# Receiver.net
KiCad netlist of a schematic drawn in Altium Designer
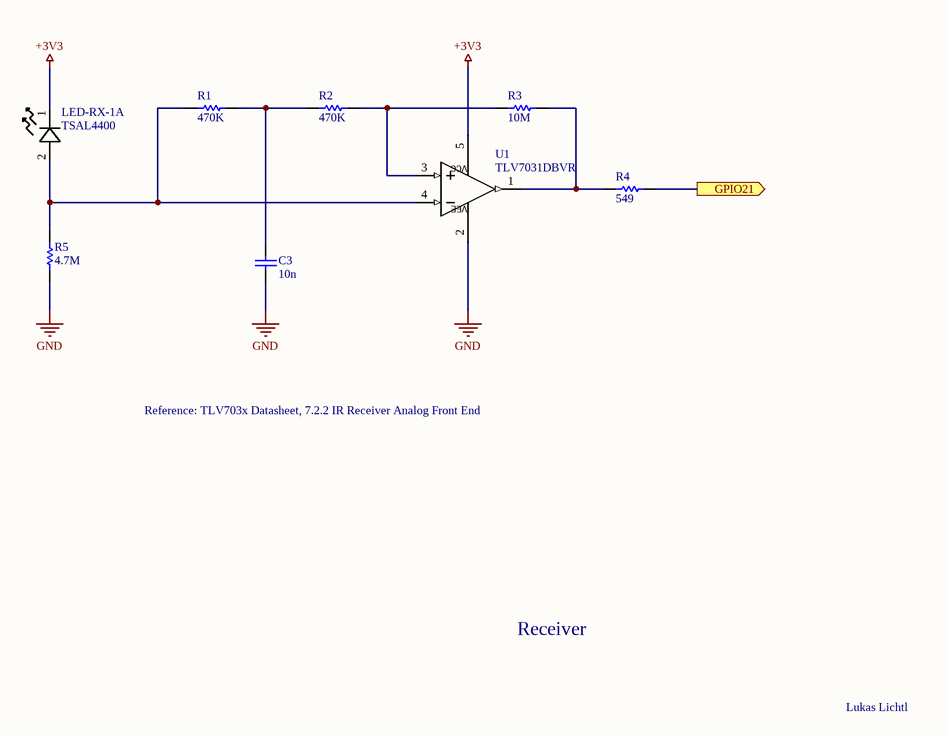
[diagram p0: Receiver.SchDoc]

(export (version "E")
  (design (tool "Eeschema 10.0.6"))
  (components
    (comp (ref "C3")
      (value "10n")
      (footprint "CAPC1608X90X35LL15T15")
      (fields
        (field (name "MANUFACTURER") "AVX Interconnect / Elco")
        (field (name "PART NUMBER") "0603ZC101KAT2A")
      )
      (libsource (lib "Altium Content Vault") (part "CAP"))
    )
    (comp (ref "LED-RX-1")
      (value "TSAL4400")
      (footprint "LED_RADIAL_TSAL4400")
      (description "Description")
      (fields (field (name "COPYRIGHT") "Copyright (C) 2025 Ultra Librarian. All rights reserved."))
      (libsource (lib "TSAL4400") (part "TSAL4400"))
    )
    (comp (ref "R1")
      (value "470K")
      (footprint "RESC1608X55X25NL10T15")
      (fields (field (name "MANUFACTURER") "Yageo") (field (name "PART NUMBER") "RC0603FR-07549RL"))
      (libsource (lib "Altium Content Vault") (part "RES"))
    )
    (comp (ref "R2")
      (value "470K")
      (footprint "RESC1608X55X25NL10T15")
      (fields (field (name "MANUFACTURER") "Yageo") (field (name "PART NUMBER") "RC0603FR-07549RL"))
      (libsource (lib "Altium Content Vault") (part "RES"))
    )
    (comp (ref "R3")
      (value "10M")
      (footprint "RESC1608X55X25NL10T15")
      (fields (field (name "MANUFACTURER") "Yageo") (field (name "PART NUMBER") "RC0603FR-07549RL"))
      (libsource (lib "Altium Content Vault") (part "RES"))
    )
    (comp (ref "R4")
      (value "549")
      (footprint "RESC1608X55X25NL10T15")
      (fields (field (name "MANUFACTURER") "Yageo") (field (name "PART NUMBER") "RC0603FR-07549RL"))
      (libsource (lib "Altium Content Vault") (part "RES"))
    )
    (comp (ref "R5")
      (value "4.7M")
      (footprint "RESC1608X55X25NL10T15")
      (fields (field (name "MANUFACTURER") "Yageo") (field (name "PART NUMBER") "RC0603FR-07549RL"))
      (libsource (lib "Altium Content Vault") (part "RES"))
    )
    (comp (ref "U1")
      (value "TLV7031DBVR")
      (footprint "DBV0005A_N")
      (description "Nanopower, small size comparator with push-pull output 5-SOT-23 -40 to 125")
      (fields (field (name "COPYRIGHT") "Copyright (C) 2026 Ultra Librarian. All rights reserved."))
      (libsource (lib "TLV7031DBVR!TLV7031DBVR") (part "TLV7031DBVR"))
    )
  )
  (nets
    (net (code "1") (name "+3V3") (class "Default")
      (node (ref "LED-RX-1") (pin "1") (pinfunction "CAHTODE_1") (pintype "passive"))
      (node (ref "U1") (pin "5") (pinfunction "VCC_5") (pintype "power_in"))
    )
    (net (code "2") (name "/GPIO21") (class "Default")
      (node (ref "R4") (pin "2") (pinfunction "2_2") (pintype "passive"))
    )
    (net (code "3") (name "GND") (class "Default")
      (node (ref "C3") (pin "1") (pinfunction "1_1") (pintype "passive"))
      (node (ref "R5") (pin "2") (pinfunction "2_2") (pintype "passive"))
      (node (ref "U1") (pin "2") (pinfunction "VEE_2") (pintype "power_in"))
    )
    (net (code "4") (name "Net-(C3-Pad2)") (class "Default")
      (node (ref "C3") (pin "2") (pinfunction "2_2") (pintype "passive"))
      (node (ref "R1") (pin "2") (pinfunction "2_2") (pintype "passive"))
      (node (ref "R2") (pin "1") (pinfunction "1_1") (pintype "passive"))
    )
    (net (code "5") (name "Net-(LED-RX-1A-ANODE)") (class "Default")
      (node (ref "LED-RX-1") (pin "2") (pinfunction "ANODE_2") (pintype "passive"))
      (node (ref "R1") (pin "1") (pinfunction "1_1") (pintype "passive"))
      (node (ref "R5") (pin "1") (pinfunction "1_1") (pintype "passive"))
      (node (ref "U1") (pin "4") (pinfunction "IN-_4") (pintype "input"))
    )
    (net (code "6") (name "Net-(U1-IN+)") (class "Default")
      (node (ref "R2") (pin "2") (pinfunction "2_2") (pintype "passive"))
      (node (ref "R3") (pin "1") (pinfunction "1_1") (pintype "passive"))
      (node (ref "U1") (pin "3") (pinfunction "IN+_3") (pintype "input"))
    )
    (net (code "7") (name "Net-(U1-OUT)") (class "Default")
      (node (ref "R3") (pin "2") (pinfunction "2_2") (pintype "passive"))
      (node (ref "R4") (pin "1") (pinfunction "1_1") (pintype "passive"))
      (node (ref "U1") (pin "1") (pinfunction "OUT_1") (pintype "output"))
    )
  )
)
